# untitled.net
KiCad netlist of a schematic drawn in EAGLE
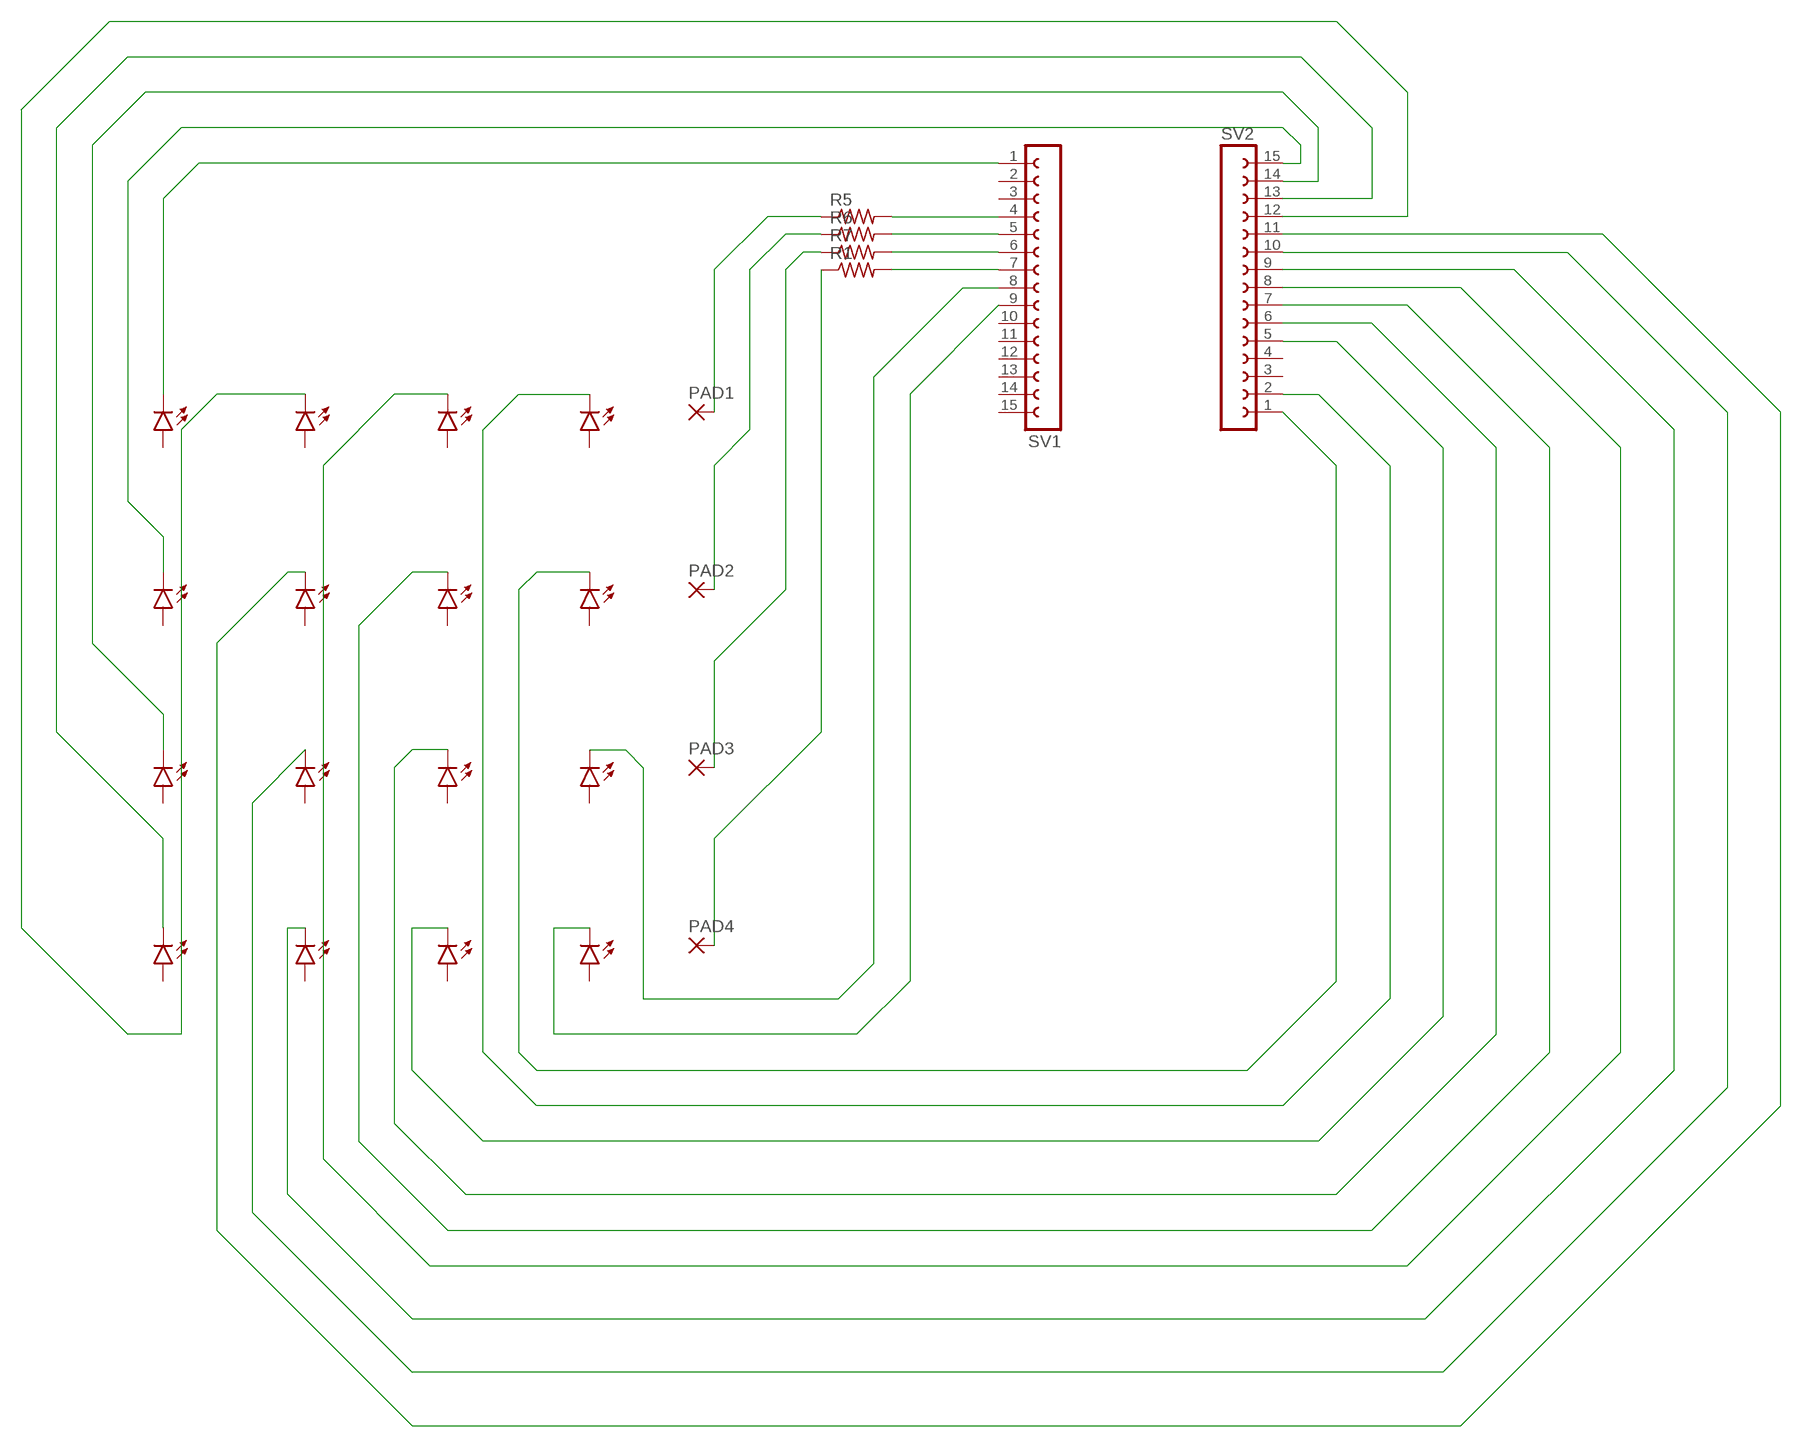
[diagram p0: schematic, sheet 1]

(export (version "E")
  (design (tool "Eeschema 10.0.6"))
  (components
    (comp (ref "LED1")
      (value "LAP4-BOTTOM")
      (footprint "eagle-import:P47F-BOTTOM")
      (libsource (lib "eagle-import") (part "P4-BOTTOMLA"))
    )
    (comp (ref "LED2")
      (value "LAP4-BOTTOM")
      (footprint "eagle-import:P47F-BOTTOM")
      (libsource (lib "eagle-import") (part "P4-BOTTOMLA"))
    )
    (comp (ref "LED3")
      (value "LAP4-BOTTOM")
      (footprint "eagle-import:P47F-BOTTOM")
      (libsource (lib "eagle-import") (part "P4-BOTTOMLA"))
    )
    (comp (ref "LED4")
      (value "LAP4-BOTTOM")
      (footprint "eagle-import:P47F-BOTTOM")
      (libsource (lib "eagle-import") (part "P4-BOTTOMLA"))
    )
    (comp (ref "LED5")
      (value "LAP4-BOTTOM")
      (footprint "eagle-import:P47F-BOTTOM")
      (libsource (lib "eagle-import") (part "P4-BOTTOMLA"))
    )
    (comp (ref "LED6")
      (value "LAP4-BOTTOM")
      (footprint "eagle-import:P47F-BOTTOM")
      (libsource (lib "eagle-import") (part "P4-BOTTOMLA"))
    )
    (comp (ref "LED7")
      (value "LAP4-BOTTOM")
      (footprint "eagle-import:P47F-BOTTOM")
      (libsource (lib "eagle-import") (part "P4-BOTTOMLA"))
    )
    (comp (ref "LED8")
      (value "LAP4-BOTTOM")
      (footprint "eagle-import:P47F-BOTTOM")
      (libsource (lib "eagle-import") (part "P4-BOTTOMLA"))
    )
    (comp (ref "LED9")
      (value "LAP4-BOTTOM")
      (footprint "eagle-import:P47F-BOTTOM")
      (libsource (lib "eagle-import") (part "P4-BOTTOMLA"))
    )
    (comp (ref "LED10")
      (value "LAP4-BOTTOM")
      (footprint "eagle-import:P47F-BOTTOM")
      (libsource (lib "eagle-import") (part "P4-BOTTOMLA"))
    )
    (comp (ref "LED11")
      (value "LAP4-BOTTOM")
      (footprint "eagle-import:P47F-BOTTOM")
      (libsource (lib "eagle-import") (part "P4-BOTTOMLA"))
    )
    (comp (ref "LED12")
      (value "LAP4-BOTTOM")
      (footprint "eagle-import:P47F-BOTTOM")
      (libsource (lib "eagle-import") (part "P4-BOTTOMLA"))
    )
    (comp (ref "LED13")
      (value "LAP4-BOTTOM")
      (footprint "eagle-import:P47F-BOTTOM")
      (libsource (lib "eagle-import") (part "P4-BOTTOMLA"))
    )
    (comp (ref "LED14")
      (value "LAP4-BOTTOM")
      (footprint "eagle-import:P47F-BOTTOM")
      (libsource (lib "eagle-import") (part "P4-BOTTOMLA"))
    )
    (comp (ref "LED15")
      (value "LAP4-BOTTOM")
      (footprint "eagle-import:P47F-BOTTOM")
      (libsource (lib "eagle-import") (part "P4-BOTTOMLA"))
    )
    (comp (ref "LED16")
      (value "LAP4-BOTTOM")
      (footprint "eagle-import:P47F-BOTTOM")
      (libsource (lib "eagle-import") (part "P4-BOTTOMLA"))
    )
    (comp (ref "PAD1")
      (value "1,6/0,8")
      (footprint "eagle-import:1,6_0,8")
      (libsource (lib "eagle-import") (part "1,6/0,8"))
    )
    (comp (ref "PAD2")
      (value "1,6/0,8")
      (footprint "eagle-import:1,6_0,8")
      (libsource (lib "eagle-import") (part "1,6/0,8"))
    )
    (comp (ref "PAD3")
      (value "1,6/0,8")
      (footprint "eagle-import:1,6_0,8")
      (libsource (lib "eagle-import") (part "1,6/0,8"))
    )
    (comp (ref "PAD4")
      (value "1,6/0,8")
      (footprint "eagle-import:1,6_0,8")
      (libsource (lib "eagle-import") (part "1,6/0,8"))
    )
    (comp (ref "R1")
      (value "FLIPFLOP-RES")
      (footprint "eagle-import:0805-THM")
      (libsource (lib "eagle-import") (part "FLIPFLOP-RES"))
    )
    (comp (ref "R5")
      (value "FLIPFLOP-RES")
      (footprint "eagle-import:0805-THM")
      (libsource (lib "eagle-import") (part "FLIPFLOP-RES"))
    )
    (comp (ref "R6")
      (value "FLIPFLOP-RES")
      (footprint "eagle-import:0805-THM")
      (libsource (lib "eagle-import") (part "FLIPFLOP-RES"))
    )
    (comp (ref "R7")
      (value "FLIPFLOP-RES")
      (footprint "eagle-import:0805-THM")
      (libsource (lib "eagle-import") (part "FLIPFLOP-RES"))
    )
    (comp (ref "SV1")
      (value "FE15-1")
      (footprint "eagle-import:FE15")
      (libsource (lib "eagle-import") (part "FE15-1"))
    )
    (comp (ref "SV2")
      (value "FE15-1")
      (footprint "eagle-import:FE15")
      (libsource (lib "eagle-import") (part "FE15-1"))
    )
  )
  (nets
    (net (code "1") (name "Net-(LED1-PadC)") (class "Default")
      (node (ref "LED1") (pin "C") (pinfunction "C_C") (pintype "passive"))
      (node (ref "SV1") (pin "8") (pinfunction "8_8") (pintype "passive"))
    )
    (net (code "2") (name "Net-(LED2-PadC)") (class "Default")
      (node (ref "LED2") (pin "C") (pinfunction "C_C") (pintype "passive"))
      (node (ref "SV2") (pin "6") (pinfunction "6_6") (pintype "passive"))
    )
    (net (code "3") (name "Net-(LED3-PadC)") (class "Default")
      (node (ref "LED3") (pin "C") (pinfunction "C_C") (pintype "passive"))
      (node (ref "SV2") (pin "1") (pinfunction "1_1") (pintype "passive"))
    )
    (net (code "4") (name "Net-(LED4-PadC)") (class "Default")
      (node (ref "LED4") (pin "C") (pinfunction "C_C") (pintype "passive"))
      (node (ref "SV2") (pin "7") (pinfunction "7_7") (pintype "passive"))
    )
    (net (code "5") (name "Net-(LED5-PadC)") (class "Default")
      (node (ref "LED5") (pin "C") (pinfunction "C_C") (pintype "passive"))
      (node (ref "SV2") (pin "2") (pinfunction "2_2") (pintype "passive"))
    )
    (net (code "6") (name "Net-(LED6-PadC)") (class "Default")
      (node (ref "LED6") (pin "C") (pinfunction "C_C") (pintype "passive"))
      (node (ref "SV2") (pin "8") (pinfunction "8_8") (pintype "passive"))
    )
    (net (code "7") (name "Net-(LED7-PadC)") (class "Default")
      (node (ref "LED7") (pin "C") (pinfunction "C_C") (pintype "passive"))
      (node (ref "SV2") (pin "10") (pinfunction "10_10") (pintype "passive"))
    )
    (net (code "8") (name "Net-(LED8-PadC)") (class "Default")
      (node (ref "LED8") (pin "C") (pinfunction "C_C") (pintype "passive"))
      (node (ref "SV2") (pin "11") (pinfunction "11_11") (pintype "passive"))
    )
    (net (code "9") (name "Net-(LED9-PadC)") (class "Default")
      (node (ref "LED9") (pin "C") (pinfunction "C_C") (pintype "passive"))
      (node (ref "SV2") (pin "12") (pinfunction "12_12") (pintype "passive"))
    )
    (net (code "10") (name "Net-(LED10-PadC)") (class "Default")
      (node (ref "LED10") (pin "C") (pinfunction "C_C") (pintype "passive"))
      (node (ref "SV2") (pin "14") (pinfunction "14_14") (pintype "passive"))
    )
    (net (code "11") (name "Net-(LED11-PadC)") (class "Default")
      (node (ref "LED11") (pin "C") (pinfunction "C_C") (pintype "passive"))
      (node (ref "SV2") (pin "15") (pinfunction "15_15") (pintype "passive"))
    )
    (net (code "12") (name "Net-(LED12-PadC)") (class "Default")
      (node (ref "LED12") (pin "C") (pinfunction "C_C") (pintype "passive"))
      (node (ref "SV1") (pin "1") (pinfunction "1_1") (pintype "passive"))
    )
    (net (code "13") (name "Net-(LED13-PadC)") (class "Default")
      (node (ref "LED13") (pin "C") (pinfunction "C_C") (pintype "passive"))
      (node (ref "SV1") (pin "9") (pinfunction "9_9") (pintype "passive"))
    )
    (net (code "14") (name "Net-(LED14-PadC)") (class "Default")
      (node (ref "LED14") (pin "C") (pinfunction "C_C") (pintype "passive"))
      (node (ref "SV2") (pin "5") (pinfunction "5_5") (pintype "passive"))
    )
    (net (code "15") (name "Net-(LED15-PadC)") (class "Default")
      (node (ref "LED15") (pin "C") (pinfunction "C_C") (pintype "passive"))
      (node (ref "SV2") (pin "9") (pinfunction "9_9") (pintype "passive"))
    )
    (net (code "16") (name "Net-(LED16-PadC)") (class "Default")
      (node (ref "LED16") (pin "C") (pinfunction "C_C") (pintype "passive"))
      (node (ref "SV2") (pin "13") (pinfunction "13_13") (pintype "passive"))
    )
    (net (code "17") (name "Net-(PAD1-P)") (class "Default")
      (node (ref "PAD1") (pin "1") (pinfunction "P_1") (pintype "passive"))
      (node (ref "R5") (pin "1") (pinfunction "1_1") (pintype "passive"))
    )
    (net (code "18") (name "Net-(PAD2-P)") (class "Default")
      (node (ref "PAD2") (pin "1") (pinfunction "P_1") (pintype "passive"))
      (node (ref "R6") (pin "1") (pinfunction "1_1") (pintype "passive"))
    )
    (net (code "19") (name "Net-(PAD3-P)") (class "Default")
      (node (ref "PAD3") (pin "1") (pinfunction "P_1") (pintype "passive"))
      (node (ref "R7") (pin "1") (pinfunction "1_1") (pintype "passive"))
    )
    (net (code "20") (name "Net-(PAD4-P)") (class "Default")
      (node (ref "PAD4") (pin "1") (pinfunction "P_1") (pintype "passive"))
      (node (ref "R1") (pin "1") (pinfunction "1_1") (pintype "passive"))
    )
    (net (code "21") (name "Net-(R1-Pad2)") (class "Default")
      (node (ref "R1") (pin "2") (pinfunction "2_2") (pintype "passive"))
      (node (ref "SV1") (pin "7") (pinfunction "7_7") (pintype "passive"))
    )
    (net (code "22") (name "Net-(R5-Pad2)") (class "Default")
      (node (ref "R5") (pin "2") (pinfunction "2_2") (pintype "passive"))
      (node (ref "SV1") (pin "4") (pinfunction "4_4") (pintype "passive"))
    )
    (net (code "23") (name "Net-(R6-Pad2)") (class "Default")
      (node (ref "R6") (pin "2") (pinfunction "2_2") (pintype "passive"))
      (node (ref "SV1") (pin "5") (pinfunction "5_5") (pintype "passive"))
    )
    (net (code "24") (name "Net-(R7-Pad2)") (class "Default")
      (node (ref "R7") (pin "2") (pinfunction "2_2") (pintype "passive"))
      (node (ref "SV1") (pin "6") (pinfunction "6_6") (pintype "passive"))
    )
    (net (code "25") (name "unconnected-(LED1-PadA)") (class "Default")
      (node (ref "LED1") (pin "A") (pinfunction "A_A") (pintype "passive"))
    )
    (net (code "26") (name "unconnected-(LED2-PadA)") (class "Default")
      (node (ref "LED2") (pin "A") (pinfunction "A_A") (pintype "passive"))
    )
    (net (code "27") (name "unconnected-(LED3-PadA)") (class "Default")
      (node (ref "LED3") (pin "A") (pinfunction "A_A") (pintype "passive"))
    )
    (net (code "28") (name "unconnected-(LED4-PadA)") (class "Default")
      (node (ref "LED4") (pin "A") (pinfunction "A_A") (pintype "passive"))
    )
    (net (code "29") (name "unconnected-(LED5-PadA)") (class "Default")
      (node (ref "LED5") (pin "A") (pinfunction "A_A") (pintype "passive"))
    )
    (net (code "30") (name "unconnected-(LED6-PadA)") (class "Default")
      (node (ref "LED6") (pin "A") (pinfunction "A_A") (pintype "passive"))
    )
    (net (code "31") (name "unconnected-(LED7-PadA)") (class "Default")
      (node (ref "LED7") (pin "A") (pinfunction "A_A") (pintype "passive"))
    )
    (net (code "32") (name "unconnected-(LED8-PadA)") (class "Default")
      (node (ref "LED8") (pin "A") (pinfunction "A_A") (pintype "passive"))
    )
    (net (code "33") (name "unconnected-(LED9-PadA)") (class "Default")
      (node (ref "LED9") (pin "A") (pinfunction "A_A") (pintype "passive"))
    )
    (net (code "34") (name "unconnected-(LED10-PadA)") (class "Default")
      (node (ref "LED10") (pin "A") (pinfunction "A_A") (pintype "passive"))
    )
    (net (code "35") (name "unconnected-(LED11-PadA)") (class "Default")
      (node (ref "LED11") (pin "A") (pinfunction "A_A") (pintype "passive"))
    )
    (net (code "36") (name "unconnected-(LED12-PadA)") (class "Default")
      (node (ref "LED12") (pin "A") (pinfunction "A_A") (pintype "passive"))
    )
    (net (code "37") (name "unconnected-(LED13-PadA)") (class "Default")
      (node (ref "LED13") (pin "A") (pinfunction "A_A") (pintype "passive"))
    )
    (net (code "38") (name "unconnected-(LED14-PadA)") (class "Default")
      (node (ref "LED14") (pin "A") (pinfunction "A_A") (pintype "passive"))
    )
    (net (code "39") (name "unconnected-(LED15-PadA)") (class "Default")
      (node (ref "LED15") (pin "A") (pinfunction "A_A") (pintype "passive"))
    )
    (net (code "40") (name "unconnected-(LED16-PadA)") (class "Default")
      (node (ref "LED16") (pin "A") (pinfunction "A_A") (pintype "passive"))
    )
    (net (code "41") (name "unconnected-(SV1-Pad2)") (class "Default")
      (node (ref "SV1") (pin "2") (pinfunction "2_2") (pintype "passive"))
    )
    (net (code "42") (name "unconnected-(SV1-Pad3)") (class "Default")
      (node (ref "SV1") (pin "3") (pinfunction "3_3") (pintype "passive"))
    )
    (net (code "43") (name "unconnected-(SV1-Pad10)") (class "Default")
      (node (ref "SV1") (pin "10") (pinfunction "10_10") (pintype "passive"))
    )
    (net (code "44") (name "unconnected-(SV1-Pad11)") (class "Default")
      (node (ref "SV1") (pin "11") (pinfunction "11_11") (pintype "passive"))
    )
    (net (code "45") (name "unconnected-(SV1-Pad12)") (class "Default")
      (node (ref "SV1") (pin "12") (pinfunction "12_12") (pintype "passive"))
    )
    (net (code "46") (name "unconnected-(SV1-Pad13)") (class "Default")
      (node (ref "SV1") (pin "13") (pinfunction "13_13") (pintype "passive"))
    )
    (net (code "47") (name "unconnected-(SV1-Pad14)") (class "Default")
      (node (ref "SV1") (pin "14") (pinfunction "14_14") (pintype "passive"))
    )
    (net (code "48") (name "unconnected-(SV1-Pad15)") (class "Default")
      (node (ref "SV1") (pin "15") (pinfunction "15_15") (pintype "passive"))
    )
    (net (code "49") (name "unconnected-(SV2-Pad3)") (class "Default")
      (node (ref "SV2") (pin "3") (pinfunction "3_3") (pintype "passive"))
    )
    (net (code "50") (name "unconnected-(SV2-Pad4)") (class "Default")
      (node (ref "SV2") (pin "4") (pinfunction "4_4") (pintype "passive"))
    )
  )
)
